# schematic.net
KiCad netlist of a schematic drawn in EAGLE
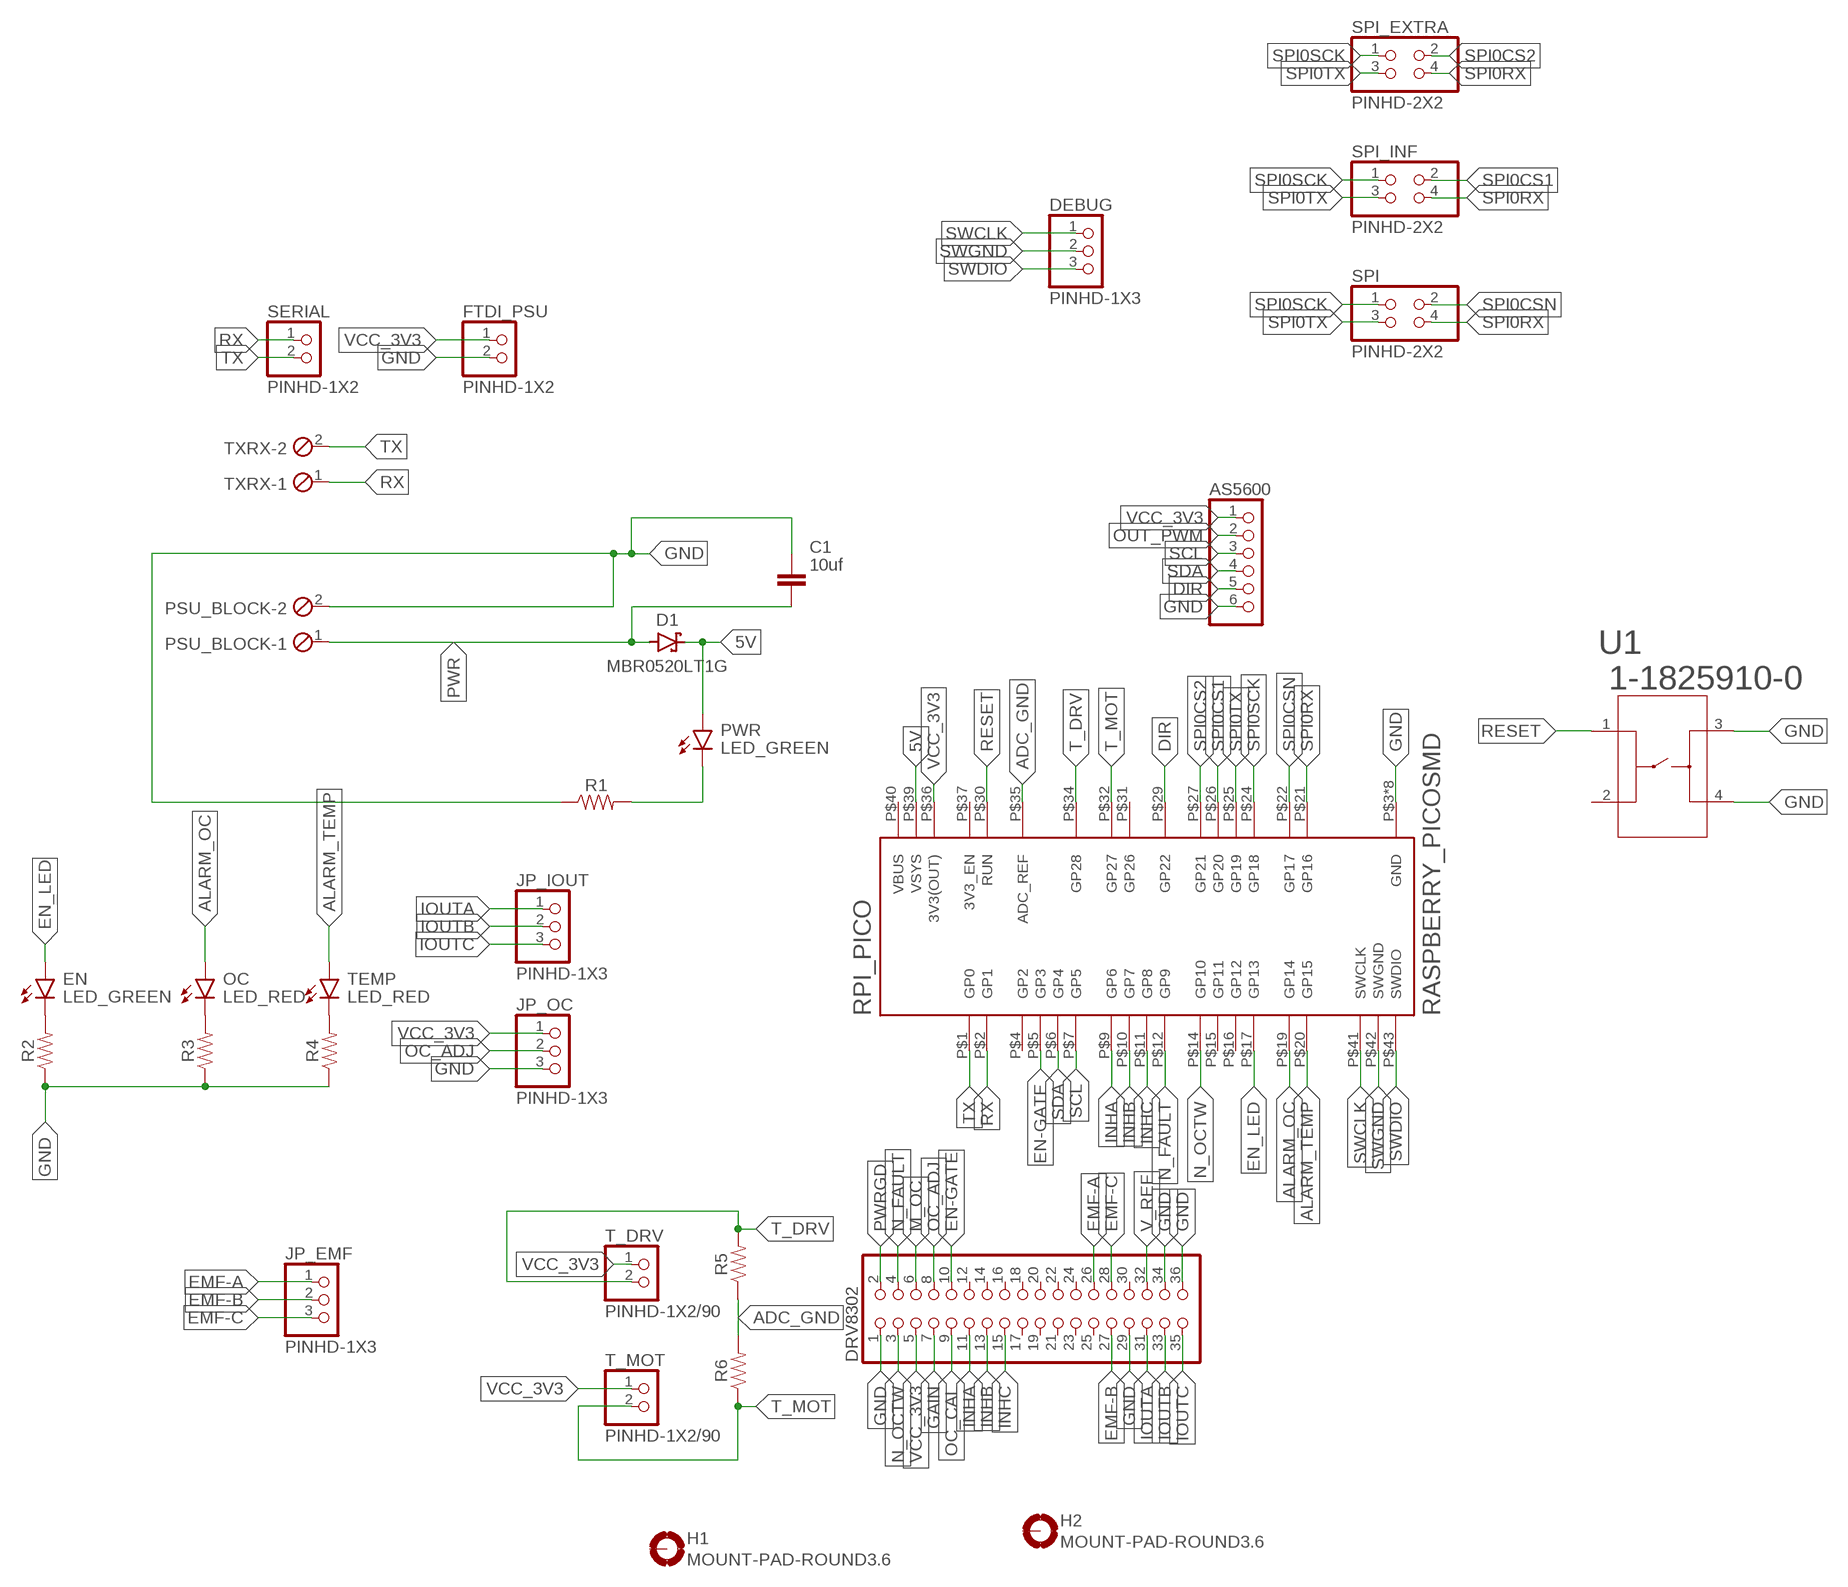
[diagram p0: schematic, sheet 1]

(export (version "E")
  (design (tool "Eeschema 10.0.6"))
  (components
    (comp (ref "AS5600")
      (value "PINHD-1X6/90")
      (footprint "eagle-import:1X06_90")
      (libsource (lib "eagle-import") (part "PINHD-1X6/90"))
    )
    (comp (ref "C1")
      (value "10uf")
      (footprint "eagle-import:CAPC2012X110")
      (libsource (lib "eagle-import") (part "CCHIP-0805(2012-METRIC)_"))
    )
    (comp (ref "D1")
      (value "MBR0520LT1G")
      (footprint "eagle-import:SODFL3718X115")
      (fields (field (name "MANUFACTURER") "ON Semiconductor"))
      (libsource (lib "eagle-import") (part "SCHOTTKY_DO-219MBR0520LT1G"))
    )
    (comp (ref "DEBUG")
      (value "PINHD-1X3")
      (footprint "eagle-import:1X03")
      (libsource (lib "eagle-import") (part "PINHD-1X3"))
    )
    (comp (ref "DRV8302")
      (value "PINHD-2X18")
      (footprint "eagle-import:2X18")
      (libsource (lib "eagle-import") (part "PINHD-2X18"))
    )
    (comp (ref "EN")
      (value "LED_GREEN")
      (footprint "eagle-import:LEDC3216X75N_FLAT-G")
      (libsource (lib "eagle-import") (part "CHIP-FLAT-G_1206"))
    )
    (comp (ref "FTDI_PSU")
      (value "PINHD-1X2")
      (footprint "eagle-import:1X02")
      (fields (field (name "MANUFACTURER") "Generic"))
      (libsource (lib "eagle-import") (part "PINHD-1X2"))
    )
    (comp (ref "H1")
      (value "MOUNT-PAD-ROUND3.6")
      (footprint "eagle-import:3,6-PAD")
      (libsource (lib "eagle-import") (part "MOUNT-PAD-ROUND3.6"))
    )
    (comp (ref "H2")
      (value "MOUNT-PAD-ROUND3.6")
      (footprint "eagle-import:3,6-PAD")
      (libsource (lib "eagle-import") (part "MOUNT-PAD-ROUND3.6"))
    )
    (comp (ref "JP_EMF")
      (value "PINHD-1X3")
      (footprint "eagle-import:1X03")
      (libsource (lib "eagle-import") (part "PINHD-1X3"))
    )
    (comp (ref "JP_IOUT")
      (value "PINHD-1X3")
      (footprint "eagle-import:1X03")
      (libsource (lib "eagle-import") (part "PINHD-1X3"))
    )
    (comp (ref "JP_OC")
      (value "PINHD-1X3")
      (footprint "eagle-import:1X03")
      (libsource (lib "eagle-import") (part "PINHD-1X3"))
    )
    (comp (ref "OC")
      (value "LED_RED")
      (footprint "eagle-import:LEDC3216X75N_FLAT-R")
      (libsource (lib "eagle-import") (part "CHIP-FLAT-R_1206"))
    )
    (comp (ref "PSU_BLOCK")
      (value "MPT2")
      (footprint "eagle-import:2POL254")
      (libsource (lib "eagle-import") (part "MPT2"))
    )
    (comp (ref "PWR")
      (value "LED_GREEN")
      (footprint "eagle-import:LEDC3216X75N_FLAT-G")
      (libsource (lib "eagle-import") (part "CHIP-FLAT-G_1206"))
    )
    (comp (ref "R1")
      (value "RESISTOR0805")
      (footprint "eagle-import:0805")
      (libsource (lib "eagle-import") (part "RESISTOR0805"))
    )
    (comp (ref "R2")
      (value "RESISTOR0805")
      (footprint "eagle-import:0805")
      (libsource (lib "eagle-import") (part "RESISTOR0805"))
    )
    (comp (ref "R3")
      (value "RESISTOR0805")
      (footprint "eagle-import:0805")
      (libsource (lib "eagle-import") (part "RESISTOR0805"))
    )
    (comp (ref "R4")
      (value "RESISTOR0805")
      (footprint "eagle-import:0805")
      (libsource (lib "eagle-import") (part "RESISTOR0805"))
    )
    (comp (ref "R5")
      (value "RESISTOR0805")
      (footprint "eagle-import:0805")
      (libsource (lib "eagle-import") (part "RESISTOR0805"))
    )
    (comp (ref "R6")
      (value "RESISTOR0805")
      (footprint "eagle-import:0805")
      (libsource (lib "eagle-import") (part "RESISTOR0805"))
    )
    (comp (ref "RPI_PICO")
      (value "RASPBERRY_PICOSMD")
      (footprint "eagle-import:PICO-PKG-SMD")
      (libsource (lib "eagle-import") (part "RASPBERRY_PICOSMD"))
    )
    (comp (ref "SERIAL")
      (value "PINHD-1X2")
      (footprint "eagle-import:1X02")
      (fields (field (name "MANUFACTURER") "Generic"))
      (libsource (lib "eagle-import") (part "PINHD-1X2"))
    )
    (comp (ref "SPI")
      (value "PINHD-2X2")
      (footprint "eagle-import:2X02")
      (libsource (lib "eagle-import") (part "PINHD-2X2"))
    )
    (comp (ref "SPI_EXTRA")
      (value "PINHD-2X2")
      (footprint "eagle-import:2X02")
      (libsource (lib "eagle-import") (part "PINHD-2X2"))
    )
    (comp (ref "SPI_INF")
      (value "PINHD-2X2")
      (footprint "eagle-import:2X02")
      (libsource (lib "eagle-import") (part "PINHD-2X2"))
    )
    (comp (ref "TEMP")
      (value "LED_RED")
      (footprint "eagle-import:LEDC3216X75N_FLAT-R")
      (libsource (lib "eagle-import") (part "CHIP-FLAT-R_1206"))
    )
    (comp (ref "TXRX")
      (value "MPT2")
      (footprint "eagle-import:2POL254")
      (libsource (lib "eagle-import") (part "MPT2"))
    )
    (comp (ref "T_DRV")
      (value "PINHD-1X2/90")
      (footprint "eagle-import:1X02_90")
      (fields (field (name "MANUFACTURER") "Generic"))
      (libsource (lib "eagle-import") (part "PINHD-1X2/90"))
    )
    (comp (ref "T_MOT")
      (value "PINHD-1X2/90")
      (footprint "eagle-import:1X02_90")
      (fields (field (name "MANUFACTURER") "Generic"))
      (libsource (lib "eagle-import") (part "PINHD-1X2/90"))
    )
    (comp (ref "U1")
      (value "1-1825910-0")
      (footprint "eagle-import:SWITCH_1-1825910-0")
      (fields (field (name "COPYRIGHT") "Copyright (C) 2016 Accelerated Designs. All rights reserved"))
      (libsource (lib "eagle-import") (part "1-1825910-0"))
    )
  )
  (nets
    (net (code "1") (name "/VBUS") (class "Default")
      (node (ref "RPI_PICO") (pin "P$40") (pinfunction "VBUS_P$40") (pintype "power_in"))
    )
    (net (code "2") (name "5V") (class "Default")
      (node (ref "D1") (pin "1") (pinfunction "C_1") (pintype "passive"))
      (node (ref "PWR") (pin "A") (pinfunction "A_A") (pintype "passive"))
      (node (ref "RPI_PICO") (pin "P$39") (pinfunction "VSYS_P$39") (pintype "power_in"))
    )
    (net (code "3") (name "ADC_GND") (class "Default")
      (node (ref "R5") (pin "1") (pinfunction "1_1") (pintype "passive"))
      (node (ref "R6") (pin "2") (pinfunction "2_2") (pintype "passive"))
      (node (ref "RPI_PICO") (pin "P$35") (pinfunction "ADC_REF_P$35") (pintype "input"))
    )
    (net (code "4") (name "ALARM_OC") (class "Default")
      (node (ref "OC") (pin "A") (pinfunction "A_A") (pintype "passive"))
      (node (ref "RPI_PICO") (pin "P$19") (pinfunction "GP14_P$19") (pintype "bidirectional"))
    )
    (net (code "5") (name "ALARM_TEMP") (class "Default")
      (node (ref "RPI_PICO") (pin "P$20") (pinfunction "GP15_P$20") (pintype "bidirectional"))
      (node (ref "TEMP") (pin "A") (pinfunction "A_A") (pintype "passive"))
    )
    (net (code "6") (name "DIR") (class "Default")
      (node (ref "AS5600") (pin "5") (pinfunction "5_5") (pintype "passive"))
      (node (ref "RPI_PICO") (pin "P$29") (pinfunction "GP22_P$29") (pintype "bidirectional"))
    )
    (net (code "7") (name "EMF-A") (class "Default")
      (node (ref "DRV8302") (pin "26") (pinfunction "26_26") (pintype "passive"))
      (node (ref "JP_EMF") (pin "1") (pinfunction "1_1") (pintype "passive"))
    )
    (net (code "8") (name "EMF-B") (class "Default")
      (node (ref "DRV8302") (pin "27") (pinfunction "27_27") (pintype "passive"))
      (node (ref "JP_EMF") (pin "2") (pinfunction "2_2") (pintype "passive"))
    )
    (net (code "9") (name "EMF-C") (class "Default")
      (node (ref "DRV8302") (pin "28") (pinfunction "28_28") (pintype "passive"))
      (node (ref "JP_EMF") (pin "3") (pinfunction "3_3") (pintype "passive"))
    )
    (net (code "10") (name "EN-GATE") (class "Default")
      (node (ref "DRV8302") (pin "10") (pinfunction "10_10") (pintype "passive"))
      (node (ref "RPI_PICO") (pin "P$5") (pinfunction "GP3_P$5") (pintype "bidirectional"))
    )
    (net (code "11") (name "EN_LED") (class "Default")
      (node (ref "EN") (pin "A") (pinfunction "A_A") (pintype "passive"))
      (node (ref "RPI_PICO") (pin "P$17") (pinfunction "GP13_P$17") (pintype "bidirectional"))
    )
    (net (code "12") (name "GAIN") (class "Default")
      (node (ref "DRV8302") (pin "7") (pinfunction "7_7") (pintype "passive"))
    )
    (net (code "13") (name "GND") (class "Default")
      (node (ref "AS5600") (pin "6") (pinfunction "6_6") (pintype "passive"))
      (node (ref "C1") (pin "1") (pinfunction "1_1") (pintype "passive"))
      (node (ref "DRV8302") (pin "1") (pinfunction "1_1") (pintype "passive"))
      (node (ref "DRV8302") (pin "29") (pinfunction "29_29") (pintype "passive"))
      (node (ref "DRV8302") (pin "34") (pinfunction "34_34") (pintype "passive"))
      (node (ref "DRV8302") (pin "36") (pinfunction "36_36") (pintype "passive"))
      (node (ref "FTDI_PSU") (pin "2") (pinfunction "2_2") (pintype "passive"))
      (node (ref "JP_OC") (pin "3") (pinfunction "3_3") (pintype "passive"))
      (node (ref "PSU_BLOCK") (pin "2") (pinfunction "1_2") (pintype "passive"))
      (node (ref "R1") (pin "1") (pinfunction "1_1") (pintype "passive"))
      (node (ref "R2") (pin "1") (pinfunction "1_1") (pintype "passive"))
      (node (ref "R3") (pin "1") (pinfunction "1_1") (pintype "passive"))
      (node (ref "R4") (pin "1") (pinfunction "1_1") (pintype "passive"))
      (node (ref "RPI_PICO") (pin "P$13") (pinfunction "GND_P$13") (pintype "power_in"))
      (node (ref "RPI_PICO") (pin "P$18") (pinfunction "GND_P$18") (pintype "power_in"))
      (node (ref "RPI_PICO") (pin "P$23") (pinfunction "GND_P$23") (pintype "power_in"))
      (node (ref "RPI_PICO") (pin "P$28") (pinfunction "GND_P$28") (pintype "power_in"))
      (node (ref "RPI_PICO") (pin "P$3") (pinfunction "GND_P$3") (pintype "power_in"))
      (node (ref "RPI_PICO") (pin "P$33") (pinfunction "GND_P$33") (pintype "power_in"))
      (node (ref "RPI_PICO") (pin "P$38") (pinfunction "GND_P$38") (pintype "power_in"))
      (node (ref "RPI_PICO") (pin "P$8") (pinfunction "GND_P$8") (pintype "power_in"))
      (node (ref "U1") (pin "3") (pinfunction "3_3") (pintype "passive"))
      (node (ref "U1") (pin "4") (pinfunction "4_4") (pintype "passive"))
    )
    (net (code "14") (name "INHA") (class "Default")
      (node (ref "DRV8302") (pin "11") (pinfunction "11_11") (pintype "passive"))
      (node (ref "RPI_PICO") (pin "P$9") (pinfunction "GP6_P$9") (pintype "bidirectional"))
    )
    (net (code "15") (name "INHB") (class "Default")
      (node (ref "DRV8302") (pin "13") (pinfunction "13_13") (pintype "passive"))
      (node (ref "RPI_PICO") (pin "P$10") (pinfunction "GP7_P$10") (pintype "bidirectional"))
    )
    (net (code "16") (name "INHC") (class "Default")
      (node (ref "DRV8302") (pin "15") (pinfunction "15_15") (pintype "passive"))
      (node (ref "RPI_PICO") (pin "P$11") (pinfunction "GP8_P$11") (pintype "bidirectional"))
    )
    (net (code "17") (name "IOUTA") (class "Default")
      (node (ref "DRV8302") (pin "31") (pinfunction "31_31") (pintype "passive"))
      (node (ref "JP_IOUT") (pin "1") (pinfunction "1_1") (pintype "passive"))
    )
    (net (code "18") (name "IOUTB") (class "Default")
      (node (ref "DRV8302") (pin "33") (pinfunction "33_33") (pintype "passive"))
      (node (ref "JP_IOUT") (pin "2") (pinfunction "2_2") (pintype "passive"))
    )
    (net (code "19") (name "IOUTC") (class "Default")
      (node (ref "DRV8302") (pin "35") (pinfunction "35_35") (pintype "passive"))
      (node (ref "JP_IOUT") (pin "3") (pinfunction "3_3") (pintype "passive"))
    )
    (net (code "20") (name "M_OC") (class "Default")
      (node (ref "DRV8302") (pin "6") (pinfunction "6_6") (pintype "passive"))
    )
    (net (code "21") (name "N_FAULT") (class "Default")
      (node (ref "DRV8302") (pin "4") (pinfunction "4_4") (pintype "passive"))
      (node (ref "RPI_PICO") (pin "P$12") (pinfunction "GP9_P$12") (pintype "bidirectional"))
    )
    (net (code "22") (name "N_OCTW") (class "Default")
      (node (ref "DRV8302") (pin "3") (pinfunction "3_3") (pintype "passive"))
      (node (ref "RPI_PICO") (pin "P$14") (pinfunction "GP10_P$14") (pintype "bidirectional"))
    )
    (net (code "23") (name "Net-(EN-PadC)") (class "Default")
      (node (ref "EN") (pin "C") (pinfunction "C_C") (pintype "passive"))
      (node (ref "R2") (pin "2") (pinfunction "2_2") (pintype "passive"))
    )
    (net (code "24") (name "Net-(OC-PadC)") (class "Default")
      (node (ref "OC") (pin "C") (pinfunction "C_C") (pintype "passive"))
      (node (ref "R3") (pin "2") (pinfunction "2_2") (pintype "passive"))
    )
    (net (code "25") (name "Net-(PWR-PadC)") (class "Default")
      (node (ref "PWR") (pin "C") (pinfunction "C_C") (pintype "passive"))
      (node (ref "R1") (pin "2") (pinfunction "2_2") (pintype "passive"))
    )
    (net (code "26") (name "Net-(R4-Pad2)") (class "Default")
      (node (ref "R4") (pin "2") (pinfunction "2_2") (pintype "passive"))
      (node (ref "TEMP") (pin "C") (pinfunction "C_C") (pintype "passive"))
    )
    (net (code "27") (name "OC_ADJ") (class "Default")
      (node (ref "DRV8302") (pin "8") (pinfunction "8_8") (pintype "passive"))
      (node (ref "JP_OC") (pin "2") (pinfunction "2_2") (pintype "passive"))
    )
    (net (code "28") (name "OC_CAL") (class "Default")
      (node (ref "DRV8302") (pin "9") (pinfunction "9_9") (pintype "passive"))
    )
    (net (code "29") (name "OUT_PWM") (class "Default")
      (node (ref "AS5600") (pin "2") (pinfunction "2_2") (pintype "passive"))
    )
    (net (code "30") (name "PWR") (class "Default")
      (node (ref "C1") (pin "2") (pinfunction "2_2") (pintype "passive"))
      (node (ref "D1") (pin "2") (pinfunction "A_2") (pintype "passive"))
      (node (ref "PSU_BLOCK") (pin "1") (pinfunction "1_1") (pintype "passive"))
    )
    (net (code "31") (name "PWRGD") (class "Default")
      (node (ref "DRV8302") (pin "2") (pinfunction "2_2") (pintype "passive"))
    )
    (net (code "32") (name "RESET") (class "Default")
      (node (ref "RPI_PICO") (pin "P$30") (pinfunction "RUN_P$30") (pintype "input"))
      (node (ref "U1") (pin "1") (pinfunction "1_1") (pintype "passive"))
    )
    (net (code "33") (name "RX") (class "Default")
      (node (ref "RPI_PICO") (pin "P$2") (pinfunction "GP1_P$2") (pintype "bidirectional"))
      (node (ref "SERIAL") (pin "1") (pinfunction "1_1") (pintype "passive"))
      (node (ref "TXRX") (pin "1") (pinfunction "1_1") (pintype "passive"))
    )
    (net (code "34") (name "SCL") (class "Default")
      (node (ref "AS5600") (pin "3") (pinfunction "3_3") (pintype "passive"))
      (node (ref "RPI_PICO") (pin "P$7") (pinfunction "GP5_P$7") (pintype "bidirectional"))
    )
    (net (code "35") (name "SDA") (class "Default")
      (node (ref "AS5600") (pin "4") (pinfunction "4_4") (pintype "passive"))
      (node (ref "RPI_PICO") (pin "P$6") (pinfunction "GP4_P$6") (pintype "bidirectional"))
    )
    (net (code "36") (name "SPI0CS1") (class "Default")
      (node (ref "RPI_PICO") (pin "P$26") (pinfunction "GP20_P$26") (pintype "bidirectional"))
      (node (ref "SPI_INF") (pin "2") (pinfunction "2_2") (pintype "passive"))
    )
    (net (code "37") (name "SPI0CS2") (class "Default")
      (node (ref "RPI_PICO") (pin "P$27") (pinfunction "GP21_P$27") (pintype "bidirectional"))
      (node (ref "SPI_EXTRA") (pin "2") (pinfunction "2_2") (pintype "passive"))
    )
    (net (code "38") (name "SPI0CSN") (class "Default")
      (node (ref "RPI_PICO") (pin "P$22") (pinfunction "GP17_P$22") (pintype "bidirectional"))
      (node (ref "SPI") (pin "2") (pinfunction "2_2") (pintype "passive"))
    )
    (net (code "39") (name "SPI0RX") (class "Default")
      (node (ref "RPI_PICO") (pin "P$21") (pinfunction "GP16_P$21") (pintype "bidirectional"))
      (node (ref "SPI") (pin "4") (pinfunction "4_4") (pintype "passive"))
      (node (ref "SPI_EXTRA") (pin "4") (pinfunction "4_4") (pintype "passive"))
      (node (ref "SPI_INF") (pin "4") (pinfunction "4_4") (pintype "passive"))
    )
    (net (code "40") (name "SPI0SCK") (class "Default")
      (node (ref "RPI_PICO") (pin "P$24") (pinfunction "GP18_P$24") (pintype "bidirectional"))
      (node (ref "SPI") (pin "1") (pinfunction "1_1") (pintype "passive"))
      (node (ref "SPI_EXTRA") (pin "1") (pinfunction "1_1") (pintype "passive"))
      (node (ref "SPI_INF") (pin "1") (pinfunction "1_1") (pintype "passive"))
    )
    (net (code "41") (name "SPI0TX") (class "Default")
      (node (ref "RPI_PICO") (pin "P$25") (pinfunction "GP19_P$25") (pintype "bidirectional"))
      (node (ref "SPI") (pin "3") (pinfunction "3_3") (pintype "passive"))
      (node (ref "SPI_EXTRA") (pin "3") (pinfunction "3_3") (pintype "passive"))
      (node (ref "SPI_INF") (pin "3") (pinfunction "3_3") (pintype "passive"))
    )
    (net (code "42") (name "SWCLK") (class "Default")
      (node (ref "DEBUG") (pin "1") (pinfunction "1_1") (pintype "passive"))
      (node (ref "RPI_PICO") (pin "P$41") (pinfunction "SWCLK_P$41") (pintype "input"))
    )
    (net (code "43") (name "SWDIO") (class "Default")
      (node (ref "DEBUG") (pin "3") (pinfunction "3_3") (pintype "passive"))
      (node (ref "RPI_PICO") (pin "P$43") (pinfunction "SWDIO_P$43") (pintype "bidirectional"))
    )
    (net (code "44") (name "SWGND") (class "Default")
      (node (ref "DEBUG") (pin "2") (pinfunction "2_2") (pintype "passive"))
      (node (ref "RPI_PICO") (pin "P$42") (pinfunction "SWGND_P$42") (pintype "power_in"))
    )
    (net (code "45") (name "TX") (class "Default")
      (node (ref "RPI_PICO") (pin "P$1") (pinfunction "GP0_P$1") (pintype "bidirectional"))
      (node (ref "SERIAL") (pin "2") (pinfunction "2_2") (pintype "passive"))
      (node (ref "TXRX") (pin "2") (pinfunction "1_2") (pintype "passive"))
    )
    (net (code "46") (name "T_DRV") (class "Default")
      (node (ref "R5") (pin "2") (pinfunction "2_2") (pintype "passive"))
      (node (ref "RPI_PICO") (pin "P$34") (pinfunction "GP28_P$34") (pintype "bidirectional"))
      (node (ref "T_DRV") (pin "2") (pinfunction "2_2") (pintype "passive"))
    )
    (net (code "47") (name "T_MOT") (class "Default")
      (node (ref "R6") (pin "1") (pinfunction "1_1") (pintype "passive"))
      (node (ref "RPI_PICO") (pin "P$32") (pinfunction "GP27_P$32") (pintype "bidirectional"))
      (node (ref "T_MOT") (pin "2") (pinfunction "2_2") (pintype "passive"))
    )
    (net (code "48") (name "VCC_3V3") (class "Default")
      (node (ref "AS5600") (pin "1") (pinfunction "1_1") (pintype "passive"))
      (node (ref "DRV8302") (pin "5") (pinfunction "5_5") (pintype "passive"))
      (node (ref "FTDI_PSU") (pin "1") (pinfunction "1_1") (pintype "passive"))
      (node (ref "JP_OC") (pin "1") (pinfunction "1_1") (pintype "passive"))
      (node (ref "RPI_PICO") (pin "P$36") (pinfunction "3V3(OUT)_P$36") (pintype "power_in"))
      (node (ref "T_DRV") (pin "1") (pinfunction "1_1") (pintype "passive"))
      (node (ref "T_MOT") (pin "1") (pinfunction "1_1") (pintype "passive"))
    )
    (net (code "49") (name "V_REF") (class "Default")
      (node (ref "DRV8302") (pin "32") (pinfunction "32_32") (pintype "passive"))
    )
    (net (code "50") (name "unconnected-(DRV8302-Pad12)") (class "Default")
      (node (ref "DRV8302") (pin "12") (pinfunction "12_12") (pintype "passive"))
    )
    (net (code "51") (name "unconnected-(DRV8302-Pad14)") (class "Default")
      (node (ref "DRV8302") (pin "14") (pinfunction "14_14") (pintype "passive"))
    )
    (net (code "52") (name "unconnected-(DRV8302-Pad16)") (class "Default")
      (node (ref "DRV8302") (pin "16") (pinfunction "16_16") (pintype "passive"))
    )
    (net (code "53") (name "unconnected-(DRV8302-Pad17)") (class "Default")
      (node (ref "DRV8302") (pin "17") (pinfunction "17_17") (pintype "passive"))
    )
    (net (code "54") (name "unconnected-(DRV8302-Pad18)") (class "Default")
      (node (ref "DRV8302") (pin "18") (pinfunction "18_18") (pintype "passive"))
    )
    (net (code "55") (name "unconnected-(DRV8302-Pad19)") (class "Default")
      (node (ref "DRV8302") (pin "19") (pinfunction "19_19") (pintype "passive"))
    )
    (net (code "56") (name "unconnected-(DRV8302-Pad20)") (class "Default")
      (node (ref "DRV8302") (pin "20") (pinfunction "20_20") (pintype "passive"))
    )
    (net (code "57") (name "unconnected-(DRV8302-Pad21)") (class "Default")
      (node (ref "DRV8302") (pin "21") (pinfunction "21_21") (pintype "passive"))
    )
    (net (code "58") (name "unconnected-(DRV8302-Pad22)") (class "Default")
      (node (ref "DRV8302") (pin "22") (pinfunction "22_22") (pintype "passive"))
    )
    (net (code "59") (name "unconnected-(DRV8302-Pad23)") (class "Default")
      (node (ref "DRV8302") (pin "23") (pinfunction "23_23") (pintype "passive"))
    )
    (net (code "60") (name "unconnected-(DRV8302-Pad24)") (class "Default")
      (node (ref "DRV8302") (pin "24") (pinfunction "24_24") (pintype "passive"))
    )
    (net (code "61") (name "unconnected-(DRV8302-Pad25)") (class "Default")
      (node (ref "DRV8302") (pin "25") (pinfunction "25_25") (pintype "passive"))
    )
    (net (code "62") (name "unconnected-(DRV8302-Pad30)") (class "Default")
      (node (ref "DRV8302") (pin "30") (pinfunction "30_30") (pintype "passive"))
    )
    (net (code "63") (name "unconnected-(H1-MOUNT-PadB3,6)") (class "Default")
      (node (ref "H1") (pin "B3,6") (pinfunction "MOUNT_B3,6") (pintype "passive"))
    )
    (net (code "64") (name "unconnected-(H2-MOUNT-PadB3,6)") (class "Default")
      (node (ref "H2") (pin "B3,6") (pinfunction "MOUNT_B3,6") (pintype "passive"))
    )
    (net (code "65") (name "unconnected-(RPI_PICO-3V3_EN-PadP$37)") (class "Default")
      (node (ref "RPI_PICO") (pin "P$37") (pinfunction "3V3_EN_P$37") (pintype "input"))
    )
    (net (code "66") (name "unconnected-(RPI_PICO-GP2-PadP$4)") (class "Default")
      (node (ref "RPI_PICO") (pin "P$4") (pinfunction "GP2_P$4") (pintype "bidirectional"))
    )
    (net (code "67") (name "unconnected-(RPI_PICO-GP11-PadP$15)") (class "Default")
      (node (ref "RPI_PICO") (pin "P$15") (pinfunction "GP11_P$15") (pintype "bidirectional"))
    )
    (net (code "68") (name "unconnected-(RPI_PICO-GP12-PadP$16)") (class "Default")
      (node (ref "RPI_PICO") (pin "P$16") (pinfunction "GP12_P$16") (pintype "bidirectional"))
    )
    (net (code "69") (name "unconnected-(RPI_PICO-GP26-PadP$31)") (class "Default")
      (node (ref "RPI_PICO") (pin "P$31") (pinfunction "GP26_P$31") (pintype "bidirectional"))
    )
    (net (code "70") (name "unconnected-(U1-Pad2)") (class "Default")
      (node (ref "U1") (pin "2") (pinfunction "2_2") (pintype "passive"))
    )
  )
)
